# Siren_Amp.net
KiCad netlist of a schematic drawn in EasyEDA
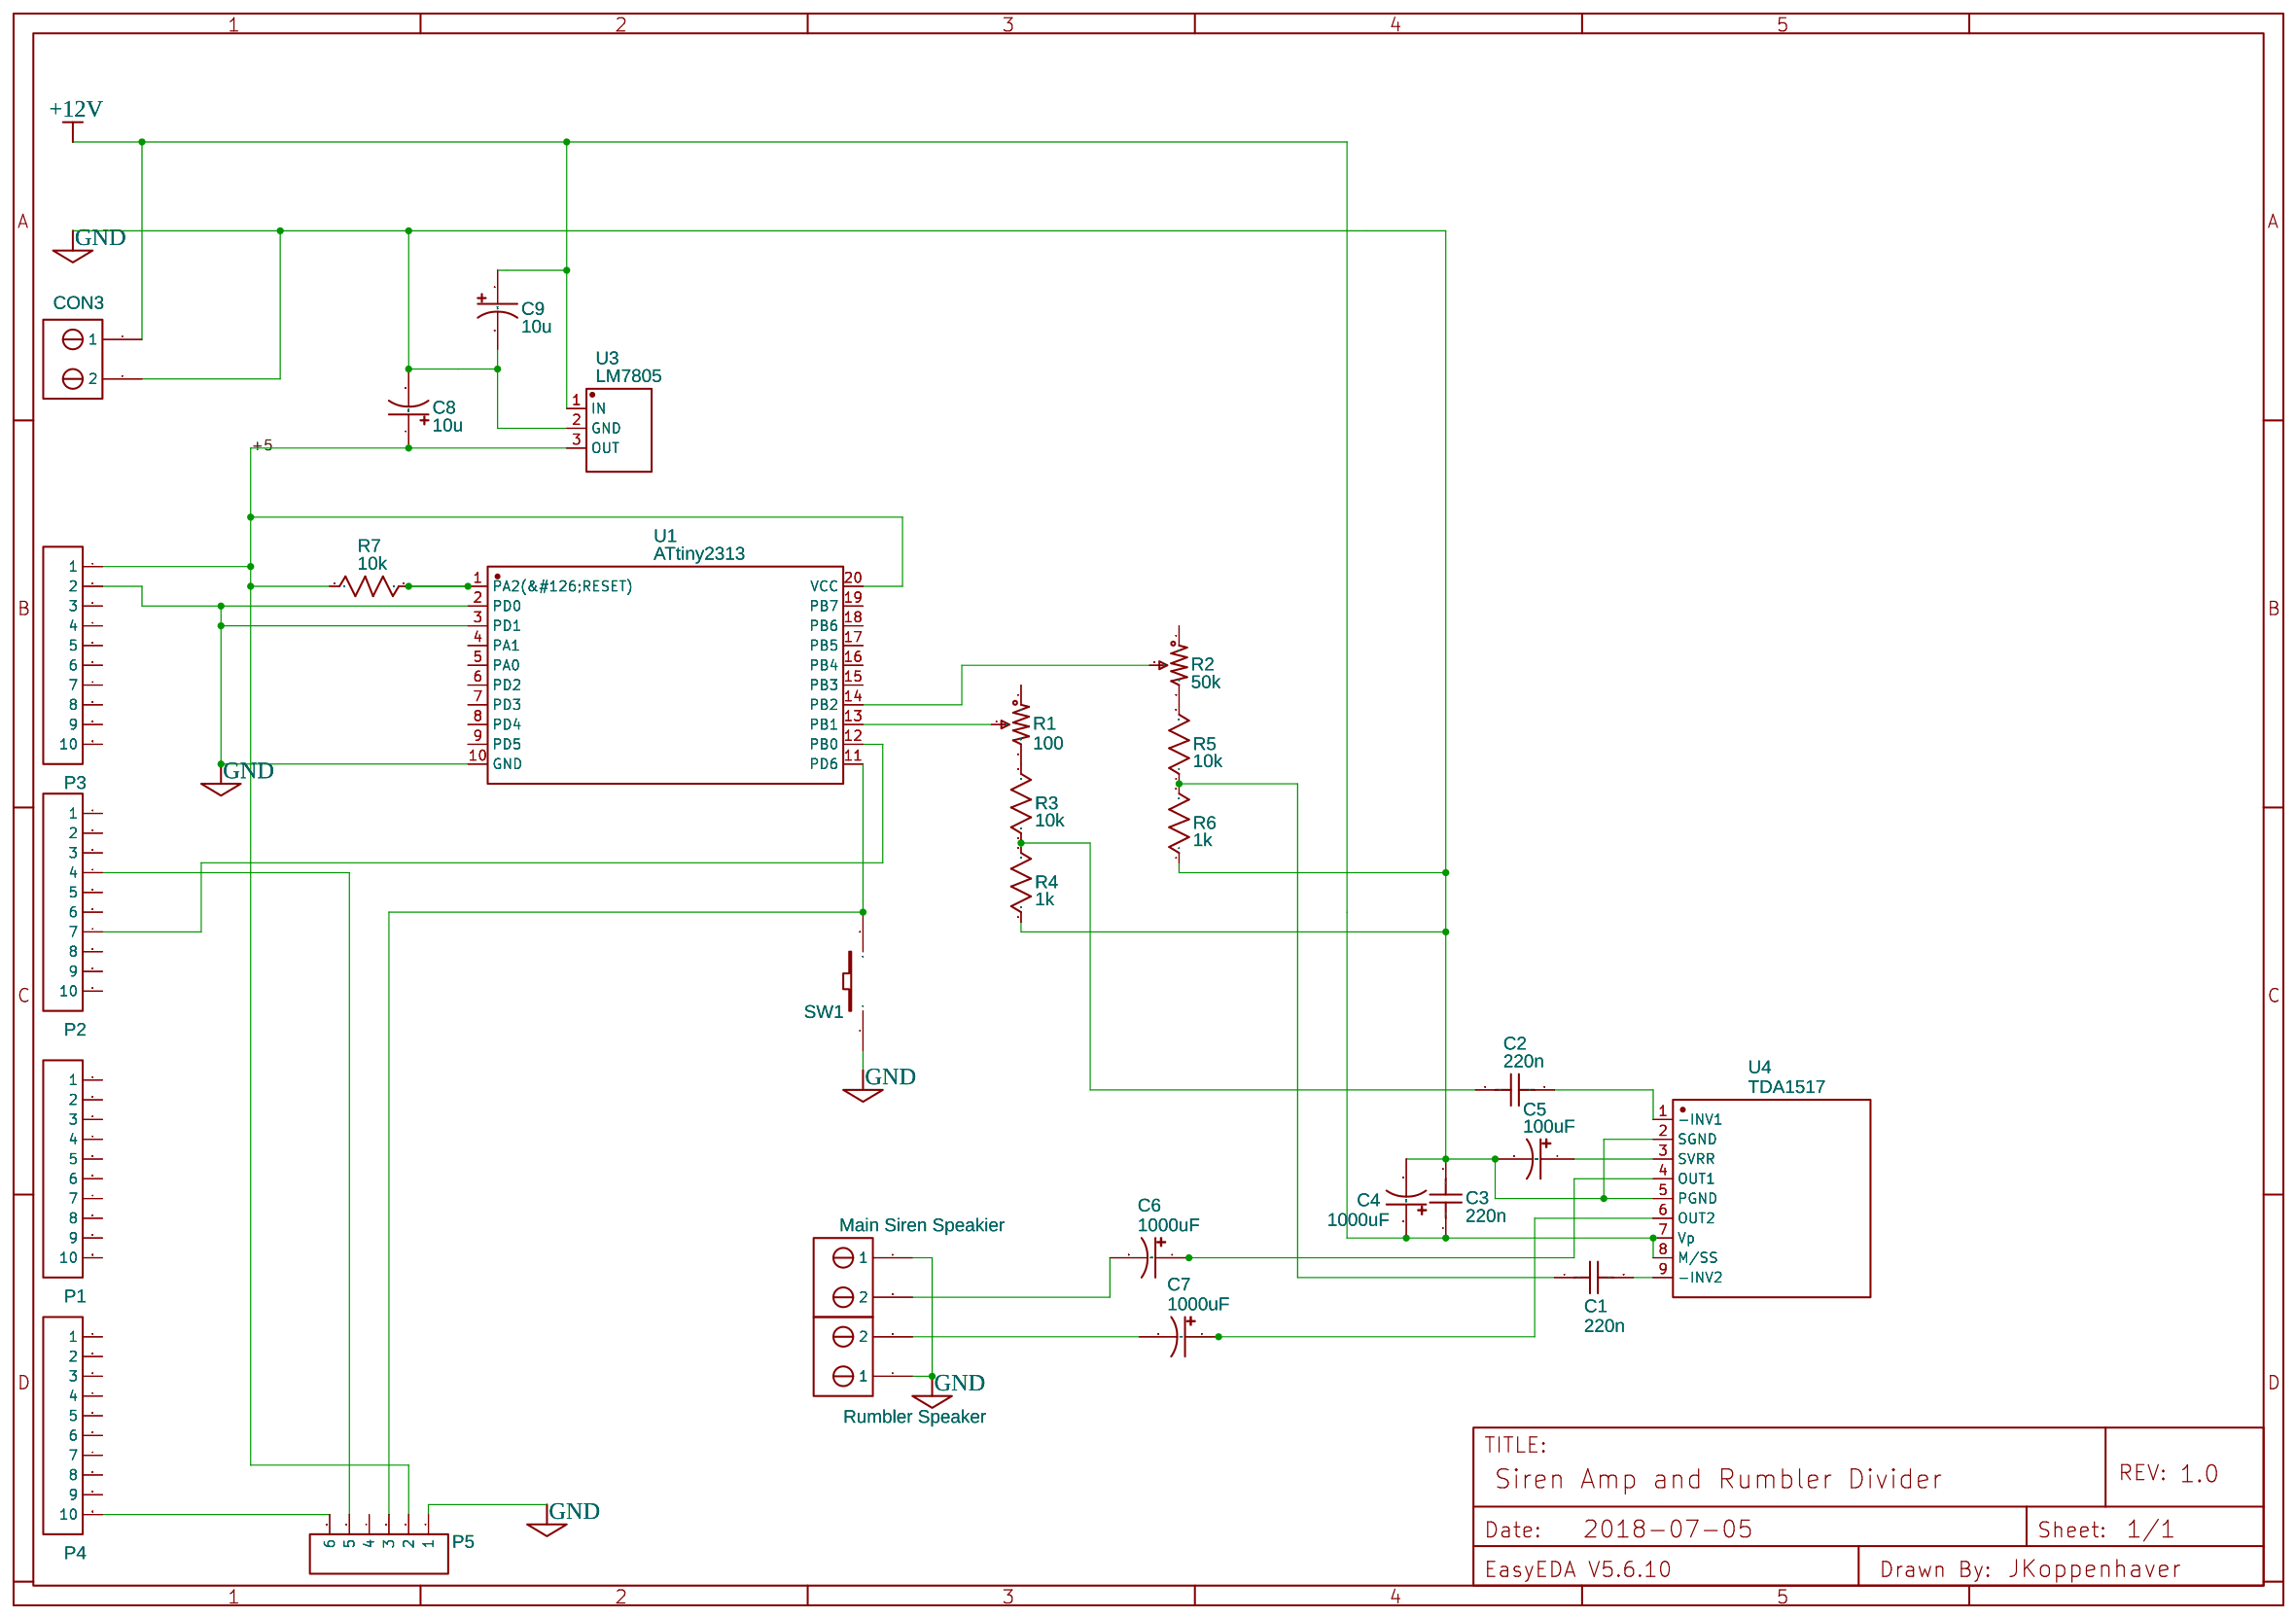
[diagram p0: schematic sheet]

(export (version "E")
  (design (tool "Eeschema 10.0.6"))
  (components
    (comp (ref "C1")
      (value "220n")
      (fields (field (name "BOM_Manufacturer Part") "?"))
      (libsource (lib "") (part "Cap_RAD-0.1_US"))
    )
    (comp (ref "C2")
      (value "220n")
      (fields (field (name "BOM_Manufacturer Part") "?"))
      (libsource (lib "") (part "Cap_RAD-0.1_US_2"))
    )
    (comp (ref "C3")
      (value "220n")
      (fields (field (name "BOM_Manufacturer Part") "?"))
      (libsource (lib "") (part "Cap_RAD-0.1_US_1"))
    )
    (comp (ref "C4")
      (value "1000uF")
      (fields (field (name "BOM_Manufacturer Part") "?"))
      (libsource (lib "") (part "Cap_Electrolytic(TH)_D3.0XF1.5_US_3"))
    )
    (comp (ref "C5")
      (value "100uF")
      (fields (field (name "BOM_Manufacturer Part") "?"))
      (libsource (lib "") (part "Cap_Electrolytic(TH)_D3.0XF1.5_US"))
    )
    (comp (ref "C6")
      (value "1000uF")
      (fields (field (name "BOM_Manufacturer Part") "?"))
      (libsource (lib "") (part "Cap_Electrolytic(TH)_D3.0XF1.5_US"))
    )
    (comp (ref "C7")
      (value "1000uF")
      (fields (field (name "BOM_Manufacturer Part") "?"))
      (libsource (lib "") (part "Cap_Electrolytic(TH)_D3.0XF1.5_US"))
    )
    (comp (ref "C8")
      (value "10u")
      (fields (field (name "BOM_Manufacturer Part") "?"))
      (libsource (lib "") (part "Cap_Electrolytic(TH)_D3.0XF1.5_US_2"))
    )
    (comp (ref "C9")
      (value "10u")
      (fields (field (name "BOM_Manufacturer Part") "?"))
      (libsource (lib "") (part "Cap_Electrolytic(TH)_D3.0XF1.5_US_1"))
    )
    (comp (ref "CON1")
      (value "Main Siren Speakier")
      (fields (field (name "BOM_Manufacturer Part") "?"))
      (libsource (lib "") (part "Unknown_425_640"))
    )
    (comp (ref "CON2")
      (value "Rumbler Speaker")
      (fields (field (name "BOM_Manufacturer Part") "?"))
      (libsource (lib "") (part "Unknown_425_680"))
    )
    (comp (ref "CON3")
      (value "TBLOCK Connector 2P 3.5mm Pitch")
      (fields (field (name "BOM_Manufacturer Part") "?"))
      (libsource (lib "") (part "Unknown_35_175"))
    )
    (comp (ref "P1")
      (value "Header-Female-2.54_1x10")
      (fields
        (field (name "BOM_Manufacturer Part") "2.54mm 1*10P Straight Female header Gold-plated")
        (field (name "BOM_Supplier Part") "C35445")
      )
      (libsource (lib "") (part "Unknown_30_585"))
    )
    (comp (ref "P2")
      (value "Header-Female-2.54_1x10")
      (fields
        (field (name "BOM_Manufacturer Part") "2.54mm 1*10P Straight Female header Gold-plated")
        (field (name "BOM_Supplier Part") "C35445")
      )
      (libsource (lib "") (part "Unknown_30_450"))
    )
    (comp (ref "P3")
      (value "Header-Female-2.54_1x10")
      (fields
        (field (name "BOM_Manufacturer Part") "2.54mm 1*10P Straight Female header Gold-plated")
        (field (name "BOM_Supplier Part") "C35445")
      )
      (libsource (lib "") (part "Unknown_30_325"))
    )
    (comp (ref "P4")
      (value "Header-Female-2.54_1x10")
      (fields
        (field (name "BOM_Manufacturer Part") "2.54mm 1*10P Straight Female header Gold-plated")
        (field (name "BOM_Supplier Part") "C35445")
      )
      (libsource (lib "") (part "Unknown_30_715"))
    )
    (comp (ref "P5")
      (value "Header-Male-2.54_1x6")
      (fields (field (name "BOM_Supplier Part") "C37208"))
      (libsource (lib "") (part "Unknown_185_775"))
    )
    (comp (ref "R1")
      (value "100")
      (fields
        (field (name "BOM_Manufacturer Part") "3386P-1-101LF")
        (field (name "BOM_Supplier Part") "C125022")
      )
      (libsource (lib "") (part "3386P-1-101LF_US"))
    )
    (comp (ref "R2")
      (value "50k")
      (fields
        (field (name "BOM_Manufacturer Part") "3386P-1-101LF")
        (field (name "BOM_Supplier Part") "C125022")
      )
      (libsource (lib "") (part "3386P-1-101LF_US"))
    )
    (comp (ref "R3")
      (value "10k")
      (fields (field (name "BOM_Manufacturer Part") "?"))
      (libsource (lib "") (part "Res_AXIAL-0.3(1/8W)_US_1"))
    )
    (comp (ref "R4")
      (value "1k")
      (fields (field (name "BOM_Manufacturer Part") "?"))
      (libsource (lib "") (part "Res_AXIAL-0.3(1/8W)_US_1"))
    )
    (comp (ref "R5")
      (value "10k")
      (fields (field (name "BOM_Manufacturer Part") "?"))
      (libsource (lib "") (part "Res_AXIAL-0.3(1/8W)_US_1"))
    )
    (comp (ref "R6")
      (value "1k")
      (fields (field (name "BOM_Manufacturer Part") "?"))
      (libsource (lib "") (part "Res_AXIAL-0.3(1/8W)_US_1"))
    )
    (comp (ref "R7")
      (value "10k")
      (fields (field (name "BOM_Manufacturer Part") "?"))
      (libsource (lib "") (part "Res_AXIAL-0.3(1/8W)_US"))
    )
    (comp (ref "SW1")
      (value "EVQ22705R")
      (fields (field (name "BOM_Supplier Part") "C79156"))
      (libsource (lib "") (part "Unknown_430_490"))
    )
    (comp (ref "U1")
      (value "ATtiny2313")
      (fields (field (name "BOM_Manufacturer Part") "?"))
      (libsource (lib "") (part "Unknown_240_280"))
    )
    (comp (ref "U3")
      (value "LM7805")
      (fields
        (field (name "BOM_Manufacturer Part") "LM7805CT/NOPB")
        (field (name "BOM_Supplier Part") "C50931")
      )
      (libsource (lib "") (part "Unknown_300_210"))
    )
    (comp (ref "U4")
      (value "TDA1517")
      (fields (field (name "BOM_Manufacturer Part") "?"))
      (libsource (lib "") (part "Unknown_840_550"))
    )
  )
  (nets
    (net (code "1") (name "+12V") (class "Default")
      (node (ref "C3") (pin "1") (pinfunction "1_1") (pintype "unspecified"))
      (node (ref "C4") (pin "1") (pinfunction "1_1") (pintype "unspecified"))
      (node (ref "C9") (pin "1") (pinfunction "1_1") (pintype "unspecified"))
      (node (ref "CON3") (pin "1") (pinfunction "1_1") (pintype "unspecified"))
      (node (ref "U3") (pin "1") (pinfunction "IN_1") (pintype "unspecified"))
      (node (ref "U4") (pin "7") (pinfunction "Vp_7") (pintype "unspecified"))
      (node (ref "U4") (pin "8") (pinfunction "M/SS_8") (pintype "unspecified"))
    )
    (net (code "2") (name "/+5") (class "Default")
      (node (ref "C8") (pin "1") (pinfunction "1_1") (pintype "unspecified"))
      (node (ref "P3") (pin "1") (pinfunction "1_1") (pintype "input"))
      (node (ref "P5") (pin "2") (pinfunction "2_2") (pintype "input"))
      (node (ref "R7") (pin "1") (pinfunction "1_1") (pintype "unspecified"))
      (node (ref "U1") (pin "20") (pinfunction "VCC_20") (pintype "unspecified"))
      (node (ref "U3") (pin "3") (pinfunction "OUT_3") (pintype "unspecified"))
    )
    (net (code "3") (name "GND") (class "Default")
      (node (ref "C3") (pin "2") (pinfunction "2_2") (pintype "unspecified"))
      (node (ref "C4") (pin "2") (pinfunction "2_2") (pintype "unspecified"))
      (node (ref "C5") (pin "2") (pinfunction "2_2") (pintype "unspecified"))
      (node (ref "C8") (pin "2") (pinfunction "2_2") (pintype "unspecified"))
      (node (ref "C9") (pin "2") (pinfunction "2_2") (pintype "unspecified"))
      (node (ref "CON1") (pin "1") (pinfunction "1_1") (pintype "unspecified"))
      (node (ref "CON2") (pin "1") (pinfunction "1_1") (pintype "unspecified"))
      (node (ref "CON3") (pin "2") (pinfunction "2_2") (pintype "unspecified"))
      (node (ref "P3") (pin "2") (pinfunction "2_2") (pintype "input"))
      (node (ref "P5") (pin "1") (pinfunction "1_1") (pintype "input"))
      (node (ref "R4") (pin "1") (pinfunction "1_1") (pintype "unspecified"))
      (node (ref "R6") (pin "1") (pinfunction "1_1") (pintype "unspecified"))
      (node (ref "SW1") (pin "1") (pinfunction "1_1") (pintype "input"))
      (node (ref "U1") (pin "10") (pinfunction "GND_10") (pintype "unspecified"))
      (node (ref "U1") (pin "2") (pinfunction "PD0_2") (pintype "unspecified"))
      (node (ref "U1") (pin "3") (pinfunction "PD1_3") (pintype "unspecified"))
      (node (ref "U3") (pin "2") (pinfunction "GND_2") (pintype "unspecified"))
      (node (ref "U4") (pin "2") (pinfunction "SGND_2") (pintype "unspecified"))
      (node (ref "U4") (pin "5") (pinfunction "PGND_5") (pintype "unspecified"))
    )
    (net (code "4") (name "Net-(C1-Pad1)") (class "Default")
      (node (ref "C1") (pin "1") (pinfunction "1_1") (pintype "unspecified"))
      (node (ref "R5") (pin "1") (pinfunction "1_1") (pintype "unspecified"))
      (node (ref "R6") (pin "2") (pinfunction "2_2") (pintype "unspecified"))
    )
    (net (code "5") (name "Net-(C2-Pad2)") (class "Default")
      (node (ref "C2") (pin "2") (pinfunction "2_2") (pintype "unspecified"))
      (node (ref "R3") (pin "1") (pinfunction "1_1") (pintype "unspecified"))
      (node (ref "R4") (pin "2") (pinfunction "2_2") (pintype "unspecified"))
    )
    (net (code "6") (name "Net-(C6-Pad2)") (class "Default")
      (node (ref "C6") (pin "2") (pinfunction "2_2") (pintype "unspecified"))
      (node (ref "CON1") (pin "2") (pinfunction "2_2") (pintype "unspecified"))
    )
    (net (code "7") (name "Net-(C7-Pad2)") (class "Default")
      (node (ref "C7") (pin "2") (pinfunction "2_2") (pintype "unspecified"))
      (node (ref "CON2") (pin "2") (pinfunction "2_2") (pintype "unspecified"))
    )
    (net (code "8") (name "Net-(P2-Pad4)") (class "Default")
      (node (ref "P2") (pin "4") (pinfunction "4_4") (pintype "input"))
      (node (ref "P5") (pin "5") (pinfunction "5_5") (pintype "input"))
    )
    (net (code "9") (name "Net-(P4-Pad10)") (class "Default")
      (node (ref "P4") (pin "10") (pinfunction "10_10") (pintype "input"))
      (node (ref "P5") (pin "6") (pinfunction "6_6") (pintype "input"))
    )
    (net (code "10") (name "Net-(R1-Pad3)") (class "Default")
      (node (ref "R1") (pin "3") (pinfunction "3_3") (pintype "unspecified"))
      (node (ref "R3") (pin "2") (pinfunction "2_2") (pintype "unspecified"))
    )
    (net (code "11") (name "Net-(R2-Pad3)") (class "Default")
      (node (ref "R2") (pin "3") (pinfunction "3_3") (pintype "unspecified"))
      (node (ref "R5") (pin "2") (pinfunction "2_2") (pintype "unspecified"))
    )
    (net (code "12") (name "Net-(U1-PA2(&#126;RESET))") (class "Default")
      (node (ref "R7") (pin "2") (pinfunction "2_2") (pintype "unspecified"))
      (node (ref "U1") (pin "1") (pinfunction "PA2(&#126;RESET)_1") (pintype "unspecified"))
    )
    (net (code "13") (name "Net-(U1-PB0)") (class "Default")
      (node (ref "P2") (pin "7") (pinfunction "7_7") (pintype "input"))
      (node (ref "U1") (pin "12") (pinfunction "PB0_12") (pintype "unspecified"))
    )
    (net (code "14") (name "Net-(U1-PB1)") (class "Default")
      (node (ref "R1") (pin "2") (pinfunction "2_2") (pintype "unspecified"))
      (node (ref "U1") (pin "13") (pinfunction "PB1_13") (pintype "unspecified"))
    )
    (net (code "15") (name "Net-(U1-PB2)") (class "Default")
      (node (ref "R2") (pin "2") (pinfunction "2_2") (pintype "unspecified"))
      (node (ref "U1") (pin "14") (pinfunction "PB2_14") (pintype "unspecified"))
    )
    (net (code "16") (name "Net-(U1-PD6)") (class "Default")
      (node (ref "P5") (pin "3") (pinfunction "3_3") (pintype "input"))
      (node (ref "SW1") (pin "2") (pinfunction "2_2") (pintype "input"))
      (node (ref "U1") (pin "11") (pinfunction "PD6_11") (pintype "unspecified"))
    )
    (net (code "17") (name "Net-(U4--INV1)") (class "Default")
      (node (ref "C2") (pin "1") (pinfunction "1_1") (pintype "unspecified"))
      (node (ref "U4") (pin "1") (pinfunction "-INV1_1") (pintype "unspecified"))
    )
    (net (code "18") (name "Net-(U4--INV2)") (class "Default")
      (node (ref "C1") (pin "2") (pinfunction "2_2") (pintype "unspecified"))
      (node (ref "U4") (pin "9") (pinfunction "-INV2_9") (pintype "unspecified"))
    )
    (net (code "19") (name "Net-(U4-OUT1)") (class "Default")
      (node (ref "C6") (pin "1") (pinfunction "1_1") (pintype "unspecified"))
      (node (ref "U4") (pin "4") (pinfunction "OUT1_4") (pintype "unspecified"))
    )
    (net (code "20") (name "Net-(U4-OUT2)") (class "Default")
      (node (ref "C7") (pin "1") (pinfunction "1_1") (pintype "unspecified"))
      (node (ref "U4") (pin "6") (pinfunction "OUT2_6") (pintype "unspecified"))
    )
    (net (code "21") (name "Net-(U4-SVRR)") (class "Default")
      (node (ref "C5") (pin "1") (pinfunction "1_1") (pintype "unspecified"))
      (node (ref "U4") (pin "3") (pinfunction "SVRR_3") (pintype "unspecified"))
    )
    (net (code "22") (name "unconnected-(P1-Pad1)") (class "Default")
      (node (ref "P1") (pin "1") (pinfunction "1_1") (pintype "input"))
    )
    (net (code "23") (name "unconnected-(P1-Pad2)") (class "Default")
      (node (ref "P1") (pin "2") (pinfunction "2_2") (pintype "input"))
    )
    (net (code "24") (name "unconnected-(P1-Pad3)") (class "Default")
      (node (ref "P1") (pin "3") (pinfunction "3_3") (pintype "input"))
    )
    (net (code "25") (name "unconnected-(P1-Pad4)") (class "Default")
      (node (ref "P1") (pin "4") (pinfunction "4_4") (pintype "input"))
    )
    (net (code "26") (name "unconnected-(P1-Pad5)") (class "Default")
      (node (ref "P1") (pin "5") (pinfunction "5_5") (pintype "input"))
    )
    (net (code "27") (name "unconnected-(P1-Pad6)") (class "Default")
      (node (ref "P1") (pin "6") (pinfunction "6_6") (pintype "input"))
    )
    (net (code "28") (name "unconnected-(P1-Pad7)") (class "Default")
      (node (ref "P1") (pin "7") (pinfunction "7_7") (pintype "input"))
    )
    (net (code "29") (name "unconnected-(P1-Pad8)") (class "Default")
      (node (ref "P1") (pin "8") (pinfunction "8_8") (pintype "input"))
    )
    (net (code "30") (name "unconnected-(P1-Pad9)") (class "Default")
      (node (ref "P1") (pin "9") (pinfunction "9_9") (pintype "input"))
    )
    (net (code "31") (name "unconnected-(P1-Pad10)") (class "Default")
      (node (ref "P1") (pin "10") (pinfunction "10_10") (pintype "input"))
    )
    (net (code "32") (name "unconnected-(P2-Pad1)") (class "Default")
      (node (ref "P2") (pin "1") (pinfunction "1_1") (pintype "input"))
    )
    (net (code "33") (name "unconnected-(P2-Pad2)") (class "Default")
      (node (ref "P2") (pin "2") (pinfunction "2_2") (pintype "input"))
    )
    (net (code "34") (name "unconnected-(P2-Pad3)") (class "Default")
      (node (ref "P2") (pin "3") (pinfunction "3_3") (pintype "input"))
    )
    (net (code "35") (name "unconnected-(P2-Pad5)") (class "Default")
      (node (ref "P2") (pin "5") (pinfunction "5_5") (pintype "input"))
    )
    (net (code "36") (name "unconnected-(P2-Pad6)") (class "Default")
      (node (ref "P2") (pin "6") (pinfunction "6_6") (pintype "input"))
    )
    (net (code "37") (name "unconnected-(P2-Pad8)") (class "Default")
      (node (ref "P2") (pin "8") (pinfunction "8_8") (pintype "input"))
    )
    (net (code "38") (name "unconnected-(P2-Pad9)") (class "Default")
      (node (ref "P2") (pin "9") (pinfunction "9_9") (pintype "input"))
    )
    (net (code "39") (name "unconnected-(P2-Pad10)") (class "Default")
      (node (ref "P2") (pin "10") (pinfunction "10_10") (pintype "input"))
    )
    (net (code "40") (name "unconnected-(P3-Pad3)") (class "Default")
      (node (ref "P3") (pin "3") (pinfunction "3_3") (pintype "input"))
    )
    (net (code "41") (name "unconnected-(P3-Pad4)") (class "Default")
      (node (ref "P3") (pin "4") (pinfunction "4_4") (pintype "input"))
    )
    (net (code "42") (name "unconnected-(P3-Pad5)") (class "Default")
      (node (ref "P3") (pin "5") (pinfunction "5_5") (pintype "input"))
    )
    (net (code "43") (name "unconnected-(P3-Pad6)") (class "Default")
      (node (ref "P3") (pin "6") (pinfunction "6_6") (pintype "input"))
    )
    (net (code "44") (name "unconnected-(P3-Pad7)") (class "Default")
      (node (ref "P3") (pin "7") (pinfunction "7_7") (pintype "input"))
    )
    (net (code "45") (name "unconnected-(P3-Pad8)") (class "Default")
      (node (ref "P3") (pin "8") (pinfunction "8_8") (pintype "input"))
    )
    (net (code "46") (name "unconnected-(P3-Pad9)") (class "Default")
      (node (ref "P3") (pin "9") (pinfunction "9_9") (pintype "input"))
    )
    (net (code "47") (name "unconnected-(P3-Pad10)") (class "Default")
      (node (ref "P3") (pin "10") (pinfunction "10_10") (pintype "input"))
    )
    (net (code "48") (name "unconnected-(P4-Pad1)") (class "Default")
      (node (ref "P4") (pin "1") (pinfunction "1_1") (pintype "input"))
    )
    (net (code "49") (name "unconnected-(P4-Pad2)") (class "Default")
      (node (ref "P4") (pin "2") (pinfunction "2_2") (pintype "input"))
    )
    (net (code "50") (name "unconnected-(P4-Pad3)") (class "Default")
      (node (ref "P4") (pin "3") (pinfunction "3_3") (pintype "input"))
    )
    (net (code "51") (name "unconnected-(P4-Pad4)") (class "Default")
      (node (ref "P4") (pin "4") (pinfunction "4_4") (pintype "input"))
    )
    (net (code "52") (name "unconnected-(P4-Pad5)") (class "Default")
      (node (ref "P4") (pin "5") (pinfunction "5_5") (pintype "input"))
    )
    (net (code "53") (name "unconnected-(P4-Pad6)") (class "Default")
      (node (ref "P4") (pin "6") (pinfunction "6_6") (pintype "input"))
    )
    (net (code "54") (name "unconnected-(P4-Pad7)") (class "Default")
      (node (ref "P4") (pin "7") (pinfunction "7_7") (pintype "input"))
    )
    (net (code "55") (name "unconnected-(P4-Pad8)") (class "Default")
      (node (ref "P4") (pin "8") (pinfunction "8_8") (pintype "input"))
    )
    (net (code "56") (name "unconnected-(P4-Pad9)") (class "Default")
      (node (ref "P4") (pin "9") (pinfunction "9_9") (pintype "input"))
    )
    (net (code "57") (name "unconnected-(P5-Pad4)") (class "Default")
      (node (ref "P5") (pin "4") (pinfunction "4_4") (pintype "input"))
    )
    (net (code "58") (name "unconnected-(R1-Pad1)") (class "Default")
      (node (ref "R1") (pin "1") (pinfunction "1_1") (pintype "unspecified"))
    )
    (net (code "59") (name "unconnected-(R2-Pad1)") (class "Default")
      (node (ref "R2") (pin "1") (pinfunction "1_1") (pintype "unspecified"))
    )
    (net (code "60") (name "unconnected-(U1-PA0-Pad5)") (class "Default")
      (node (ref "U1") (pin "5") (pinfunction "PA0_5") (pintype "unspecified"))
    )
    (net (code "61") (name "unconnected-(U1-PA1-Pad4)") (class "Default")
      (node (ref "U1") (pin "4") (pinfunction "PA1_4") (pintype "unspecified"))
    )
    (net (code "62") (name "unconnected-(U1-PB3-Pad15)") (class "Default")
      (node (ref "U1") (pin "15") (pinfunction "PB3_15") (pintype "unspecified"))
    )
    (net (code "63") (name "unconnected-(U1-PB4-Pad16)") (class "Default")
      (node (ref "U1") (pin "16") (pinfunction "PB4_16") (pintype "unspecified"))
    )
    (net (code "64") (name "unconnected-(U1-PB5-Pad17)") (class "Default")
      (node (ref "U1") (pin "17") (pinfunction "PB5_17") (pintype "unspecified"))
    )
    (net (code "65") (name "unconnected-(U1-PB6-Pad18)") (class "Default")
      (node (ref "U1") (pin "18") (pinfunction "PB6_18") (pintype "unspecified"))
    )
    (net (code "66") (name "unconnected-(U1-PB7-Pad19)") (class "Default")
      (node (ref "U1") (pin "19") (pinfunction "PB7_19") (pintype "unspecified"))
    )
    (net (code "67") (name "unconnected-(U1-PD2-Pad6)") (class "Default")
      (node (ref "U1") (pin "6") (pinfunction "PD2_6") (pintype "unspecified"))
    )
    (net (code "68") (name "unconnected-(U1-PD3-Pad7)") (class "Default")
      (node (ref "U1") (pin "7") (pinfunction "PD3_7") (pintype "unspecified"))
    )
    (net (code "69") (name "unconnected-(U1-PD4-Pad8)") (class "Default")
      (node (ref "U1") (pin "8") (pinfunction "PD4_8") (pintype "unspecified"))
    )
    (net (code "70") (name "unconnected-(U1-PD5-Pad9)") (class "Default")
      (node (ref "U1") (pin "9") (pinfunction "PD5_9") (pintype "unspecified"))
    )
  )
)
